# TriggerBoard_v4_rfm12b.net
KiCad netlist of a schematic drawn in EAGLE
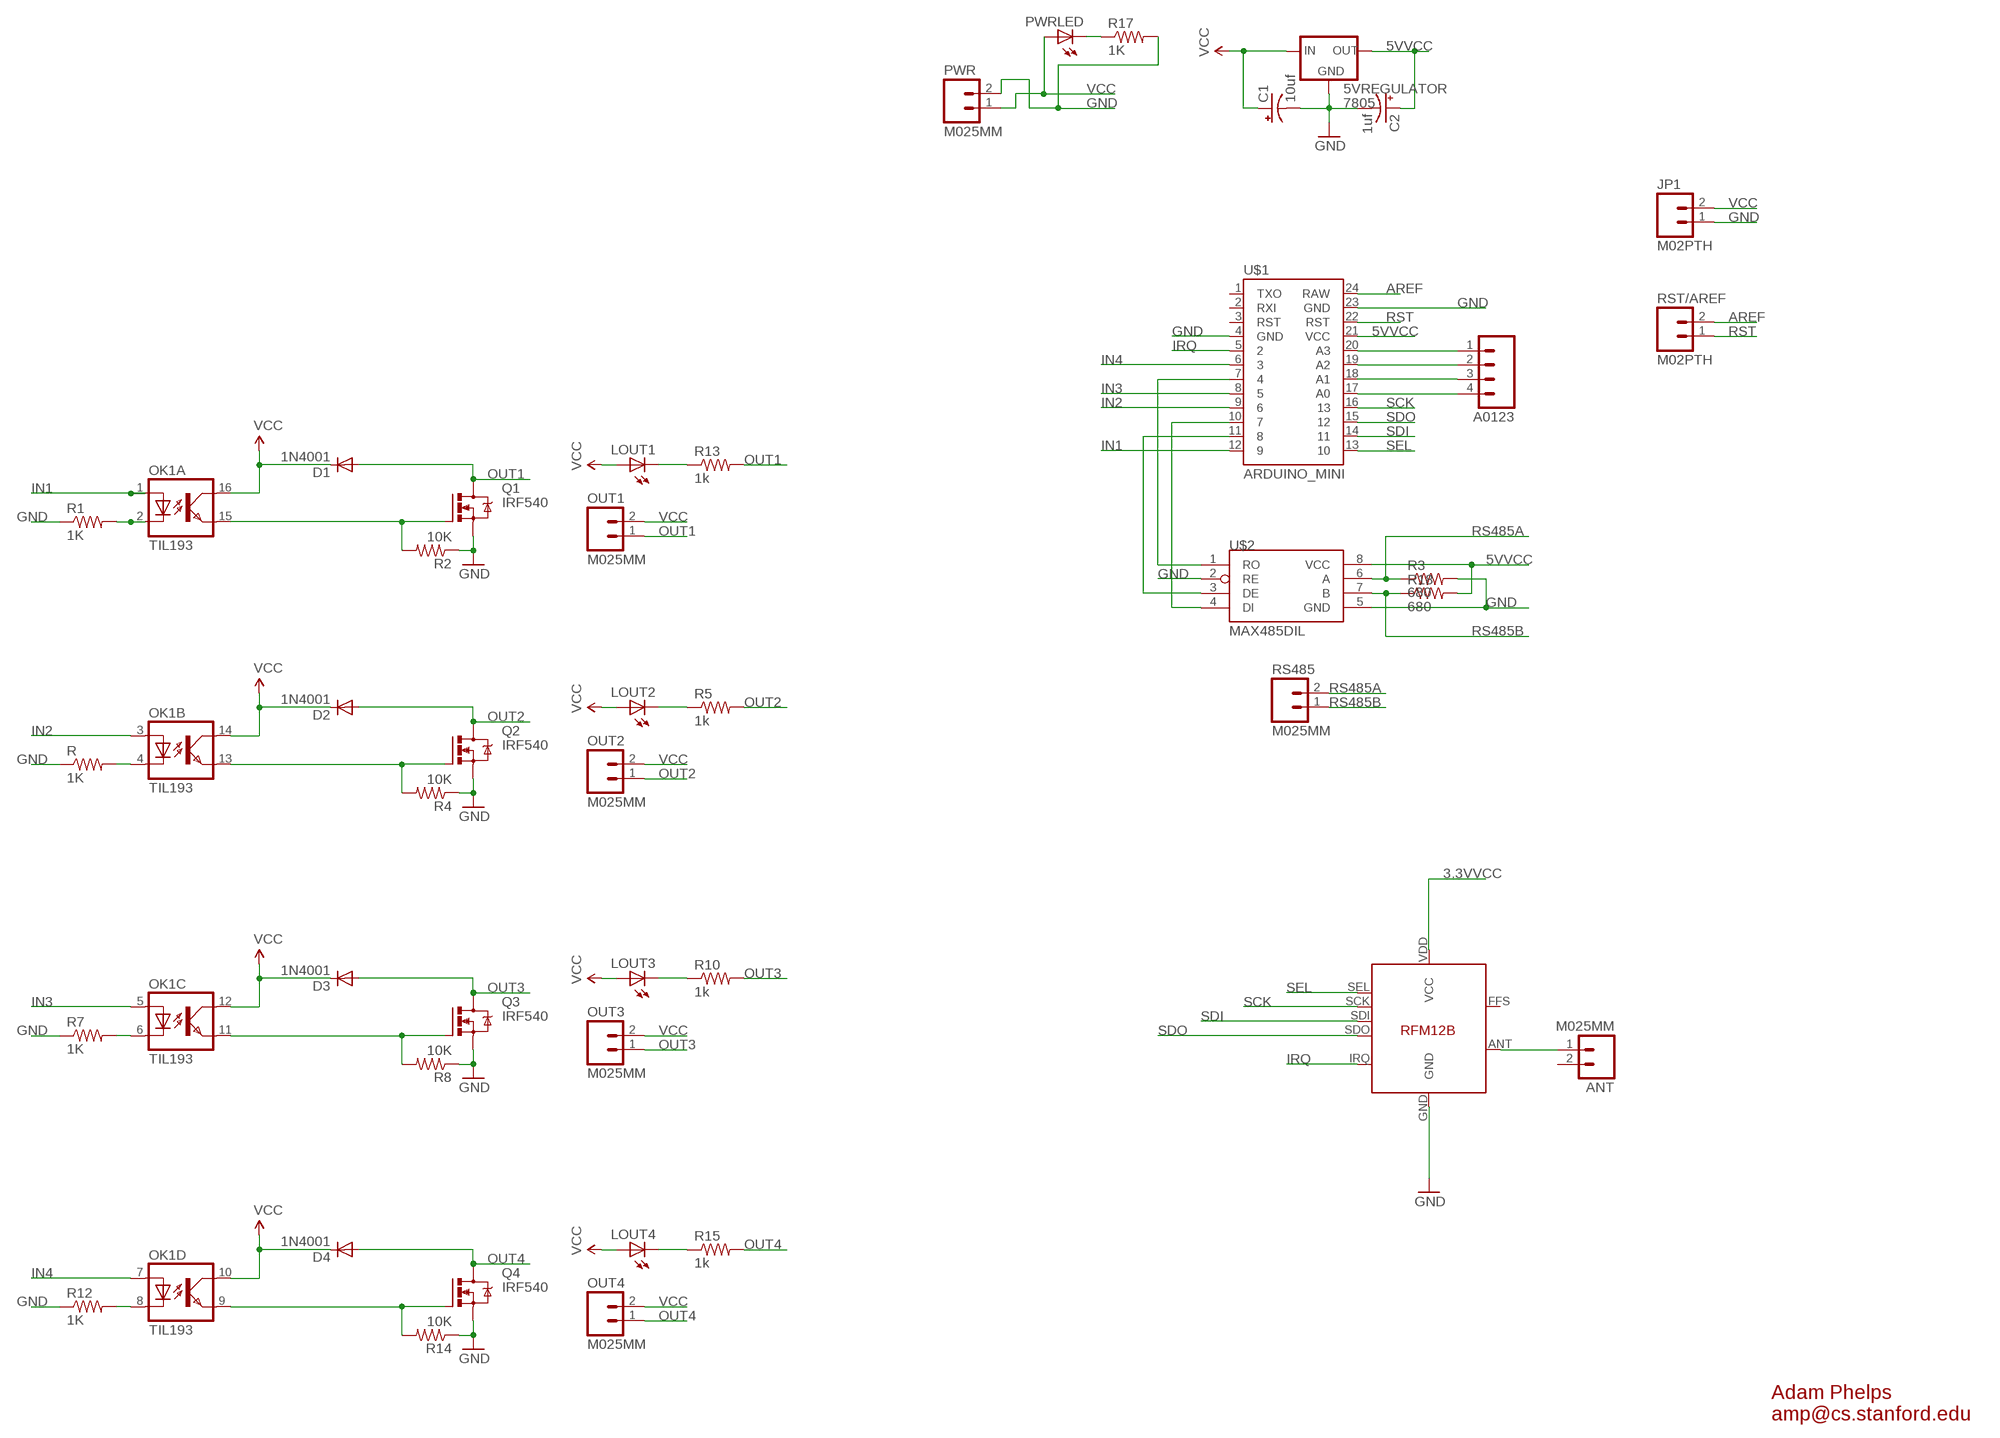
[diagram p0: schematic, sheet 1]

(export (version "E")
  (design (tool "Eeschema 10.0.6"))
  (components
    (comp (ref "5VREGULATOR")
      (value "7805")
      (footprint "eagle-import:TO220-IGO")
      (libsource (lib "eagle-import") (part "V_REG_78XXSINK"))
    )
    (comp (ref "A0123")
      (value "M04PTH")
      (footprint "eagle-import:1X04")
      (libsource (lib "eagle-import") (part "M04PTH"))
    )
    (comp (ref "ANT")
      (value "M025MM")
      (footprint "eagle-import:SCREWTERMINAL-5MM-2")
      (libsource (lib "eagle-import") (part "M025MM"))
    )
    (comp (ref "C1")
      (value "10uf")
      (footprint "eagle-import:CPOL-RADIAL-10UF-25V")
      (libsource (lib "eagle-import") (part "CAP_POLPTH2"))
    )
    (comp (ref "C2")
      (value "1uf")
      (footprint "eagle-import:CPOL-RADIAL-10UF-25V")
      (libsource (lib "eagle-import") (part "CAP_POLPTH2"))
    )
    (comp (ref "D1")
      (value "1N4001")
      (footprint "eagle-import:DIODE-1N4001")
      (libsource (lib "eagle-import") (part "DIODEPTH"))
    )
    (comp (ref "D2")
      (value "1N4001")
      (footprint "eagle-import:DIODE-1N4001")
      (libsource (lib "eagle-import") (part "DIODEPTH"))
    )
    (comp (ref "D3")
      (value "1N4001")
      (footprint "eagle-import:DIODE-1N4001")
      (libsource (lib "eagle-import") (part "DIODEPTH"))
    )
    (comp (ref "D4")
      (value "1N4001")
      (footprint "eagle-import:DIODE-1N4001")
      (libsource (lib "eagle-import") (part "DIODEPTH"))
    )
    (comp (ref "JP1")
      (value "M02PTH")
      (footprint "eagle-import:1X02")
      (libsource (lib "eagle-import") (part "M02PTH"))
    )
    (comp (ref "LOUT1")
      (value "LED3MM")
      (footprint "eagle-import:LED3MM")
      (libsource (lib "eagle-import") (part "LED3MM"))
    )
    (comp (ref "LOUT2")
      (value "LED3MM")
      (footprint "eagle-import:LED3MM")
      (libsource (lib "eagle-import") (part "LED3MM"))
    )
    (comp (ref "LOUT3")
      (value "LED3MM")
      (footprint "eagle-import:LED3MM")
      (libsource (lib "eagle-import") (part "LED3MM"))
    )
    (comp (ref "LOUT4")
      (value "LED3MM")
      (footprint "eagle-import:LED3MM")
      (libsource (lib "eagle-import") (part "LED3MM"))
    )
    (comp (ref "OK1")
      (value "TIL193")
      (footprint "eagle-import:DIL16")
      (libsource (lib "eagle-import") (part "TIL193"))
    )
    (comp (ref "OUT1")
      (value "M025MM")
      (footprint "eagle-import:SCREWTERMINAL-5MM-2")
      (libsource (lib "eagle-import") (part "M025MM"))
    )
    (comp (ref "OUT2")
      (value "M025MM")
      (footprint "eagle-import:SCREWTERMINAL-5MM-2")
      (libsource (lib "eagle-import") (part "M025MM"))
    )
    (comp (ref "OUT3")
      (value "M025MM")
      (footprint "eagle-import:SCREWTERMINAL-5MM-2")
      (libsource (lib "eagle-import") (part "M025MM"))
    )
    (comp (ref "OUT4")
      (value "M025MM")
      (footprint "eagle-import:SCREWTERMINAL-5MM-2")
      (libsource (lib "eagle-import") (part "M025MM"))
    )
    (comp (ref "PWR")
      (value "M025MM")
      (footprint "eagle-import:SCREWTERMINAL-5MM-2")
      (libsource (lib "eagle-import") (part "M025MM"))
    )
    (comp (ref "PWRLED")
      (value "LED5MM")
      (footprint "eagle-import:LED5MM")
      (libsource (lib "eagle-import") (part "LED5MM"))
    )
    (comp (ref "Q1")
      (value "IRF540")
      (footprint "eagle-import:TO220BV")
      (libsource (lib "eagle-import") (part "IRF540"))
    )
    (comp (ref "Q2")
      (value "IRF540")
      (footprint "eagle-import:TO220BV")
      (libsource (lib "eagle-import") (part "IRF540"))
    )
    (comp (ref "Q3")
      (value "IRF540")
      (footprint "eagle-import:TO220BV")
      (libsource (lib "eagle-import") (part "IRF540"))
    )
    (comp (ref "Q4")
      (value "IRF540")
      (footprint "eagle-import:TO220BV")
      (libsource (lib "eagle-import") (part "IRF540"))
    )
    (comp (ref "R")
      (value "1K")
      (footprint "eagle-import:AXIAL-0.4")
      (libsource (lib "eagle-import") (part "RESISTORPTH-1/4W"))
    )
    (comp (ref "R1")
      (value "1K")
      (footprint "eagle-import:AXIAL-0.4")
      (libsource (lib "eagle-import") (part "RESISTORPTH-1/4W"))
    )
    (comp (ref "R2")
      (value "10K")
      (footprint "eagle-import:AXIAL-0.4")
      (libsource (lib "eagle-import") (part "RESISTORPTH-1/4W"))
    )
    (comp (ref "R3")
      (value "680")
      (footprint "eagle-import:AXIAL-0.4")
      (libsource (lib "eagle-import") (part "RESISTORPTH-1/4W"))
    )
    (comp (ref "R4")
      (value "10K")
      (footprint "eagle-import:AXIAL-0.4")
      (libsource (lib "eagle-import") (part "RESISTORPTH-1/4W"))
    )
    (comp (ref "R5")
      (value "1k")
      (footprint "eagle-import:AXIAL-0.4")
      (libsource (lib "eagle-import") (part "RESISTORPTH-1/4W"))
    )
    (comp (ref "R7")
      (value "1K")
      (footprint "eagle-import:AXIAL-0.4")
      (libsource (lib "eagle-import") (part "RESISTORPTH-1/4W"))
    )
    (comp (ref "R8")
      (value "10K")
      (footprint "eagle-import:AXIAL-0.4")
      (libsource (lib "eagle-import") (part "RESISTORPTH-1/4W"))
    )
    (comp (ref "R10")
      (value "1k")
      (footprint "eagle-import:AXIAL-0.4")
      (libsource (lib "eagle-import") (part "RESISTORPTH-1/4W"))
    )
    (comp (ref "R12")
      (value "1K")
      (footprint "eagle-import:AXIAL-0.4")
      (libsource (lib "eagle-import") (part "RESISTORPTH-1/4W"))
    )
    (comp (ref "R13")
      (value "1k")
      (footprint "eagle-import:AXIAL-0.4")
      (libsource (lib "eagle-import") (part "RESISTORPTH-1/4W"))
    )
    (comp (ref "R14")
      (value "10K")
      (footprint "eagle-import:AXIAL-0.4")
      (libsource (lib "eagle-import") (part "RESISTORPTH-1/4W"))
    )
    (comp (ref "R15")
      (value "1k")
      (footprint "eagle-import:AXIAL-0.4")
      (libsource (lib "eagle-import") (part "RESISTORPTH-1/4W"))
    )
    (comp (ref "R17")
      (value "1K")
      (footprint "eagle-import:AXIAL-0.4")
      (libsource (lib "eagle-import") (part "RESISTORPTH-1/4W"))
    )
    (comp (ref "R18")
      (value "680")
      (footprint "eagle-import:AXIAL-0.4")
      (libsource (lib "eagle-import") (part "RESISTORPTH-1/4W"))
    )
    (comp (ref "RS485")
      (value "M025MM")
      (footprint "eagle-import:SCREWTERMINAL-5MM-2")
      (libsource (lib "eagle-import") (part "M025MM"))
    )
    (comp (ref "RST/AREF")
      (value "M02PTH")
      (footprint "eagle-import:1X02")
      (libsource (lib "eagle-import") (part "M02PTH"))
    )
    (comp (ref "U$1")
      (value "ARDUINO_MINI")
      (footprint "eagle-import:ARDUINO_MINI")
      (libsource (lib "eagle-import") (part "ARDUINO_MINI"))
    )
    (comp (ref "U$2")
      (value "MAX485DIL")
      (footprint "eagle-import:DIL08")
      (libsource (lib "eagle-import") (part "MAX485DIL"))
    )
    (comp (ref "U$3")
      (value "RFM12B")
      (footprint "eagle-import:RFM12B")
      (libsource (lib "eagle-import") (part "RFM12B"))
    )
  )
  (nets
    (net (code "1") (name "/3.3VVCC") (class "Default")
      (node (ref "U$3") (pin "VDD") (pinfunction "VCC_VDD") (pintype "power_in"))
    )
    (net (code "2") (name "/5VVCC") (class "Default")
      (node (ref "5VREGULATOR") (pin "OUT") (pinfunction "OUT_OUT") (pintype "output"))
      (node (ref "C2") (pin "1") (pinfunction "+_1") (pintype "passive"))
      (node (ref "R18") (pin "P$2") (pinfunction "2_P$2") (pintype "passive"))
      (node (ref "U$1") (pin "21") (pinfunction "VCC_21") (pintype "bidirectional"))
      (node (ref "U$2") (pin "8") (pinfunction "VCC_8") (pintype "bidirectional"))
    )
    (net (code "3") (name "/AREF") (class "Default")
      (node (ref "RST/AREF") (pin "2") (pinfunction "2_2") (pintype "passive"))
      (node (ref "U$1") (pin "24") (pinfunction "RAW_24") (pintype "bidirectional"))
    )
    (net (code "4") (name "/IN1") (class "Default")
      (node (ref "OK1") (pin "1") (pinfunction "A_1") (pintype "passive"))
      (node (ref "U$1") (pin "12") (pinfunction "9_12") (pintype "bidirectional"))
    )
    (net (code "5") (name "/IN2") (class "Default")
      (node (ref "OK1") (pin "3") (pinfunction "A_3") (pintype "passive"))
      (node (ref "U$1") (pin "9") (pinfunction "6_9") (pintype "bidirectional"))
    )
    (net (code "6") (name "/IN3") (class "Default")
      (node (ref "OK1") (pin "5") (pinfunction "A_5") (pintype "passive"))
      (node (ref "U$1") (pin "8") (pinfunction "5_8") (pintype "bidirectional"))
    )
    (net (code "7") (name "/IN4") (class "Default")
      (node (ref "OK1") (pin "7") (pinfunction "A_7") (pintype "passive"))
      (node (ref "U$1") (pin "6") (pinfunction "3_6") (pintype "bidirectional"))
    )
    (net (code "8") (name "/IRQ") (class "Default")
      (node (ref "U$1") (pin "5") (pinfunction "2_5") (pintype "bidirectional"))
      (node (ref "U$3") (pin "IRQ") (pinfunction "IRQ_IRQ") (pintype "open_collector"))
    )
    (net (code "9") (name "/OUT1") (class "Default")
      (node (ref "D1") (pin "A") (pinfunction "A_A") (pintype "passive"))
      (node (ref "OUT1") (pin "1") (pinfunction "1_1") (pintype "passive"))
      (node (ref "Q1") (pin "D") (pinfunction "D_D") (pintype "passive"))
      (node (ref "R13") (pin "P$2") (pinfunction "2_P$2") (pintype "passive"))
    )
    (net (code "10") (name "/OUT2") (class "Default")
      (node (ref "D2") (pin "A") (pinfunction "A_A") (pintype "passive"))
      (node (ref "OUT2") (pin "1") (pinfunction "1_1") (pintype "passive"))
      (node (ref "Q2") (pin "D") (pinfunction "D_D") (pintype "passive"))
      (node (ref "R5") (pin "P$2") (pinfunction "2_P$2") (pintype "passive"))
    )
    (net (code "11") (name "/OUT3") (class "Default")
      (node (ref "D3") (pin "A") (pinfunction "A_A") (pintype "passive"))
      (node (ref "OUT3") (pin "1") (pinfunction "1_1") (pintype "passive"))
      (node (ref "Q3") (pin "D") (pinfunction "D_D") (pintype "passive"))
      (node (ref "R10") (pin "P$2") (pinfunction "2_P$2") (pintype "passive"))
    )
    (net (code "12") (name "/OUT4") (class "Default")
      (node (ref "D4") (pin "A") (pinfunction "A_A") (pintype "passive"))
      (node (ref "OUT4") (pin "1") (pinfunction "1_1") (pintype "passive"))
      (node (ref "Q4") (pin "D") (pinfunction "D_D") (pintype "passive"))
      (node (ref "R15") (pin "P$2") (pinfunction "2_P$2") (pintype "passive"))
    )
    (net (code "13") (name "/RS485A") (class "Default")
      (node (ref "R3") (pin "P$1") (pinfunction "1_P$1") (pintype "passive"))
      (node (ref "RS485") (pin "2") (pinfunction "2_2") (pintype "passive"))
      (node (ref "U$2") (pin "6") (pinfunction "A_6") (pintype "bidirectional"))
    )
    (net (code "14") (name "/RS485B") (class "Default")
      (node (ref "R18") (pin "P$1") (pinfunction "1_P$1") (pintype "passive"))
      (node (ref "RS485") (pin "1") (pinfunction "1_1") (pintype "passive"))
      (node (ref "U$2") (pin "7") (pinfunction "B_7") (pintype "bidirectional"))
    )
    (net (code "15") (name "/RST") (class "Default")
      (node (ref "RST/AREF") (pin "1") (pinfunction "1_1") (pintype "passive"))
      (node (ref "U$1") (pin "22") (pinfunction "RST_22") (pintype "bidirectional"))
    )
    (net (code "16") (name "/SCK") (class "Default")
      (node (ref "U$1") (pin "16") (pinfunction "13_16") (pintype "bidirectional"))
      (node (ref "U$3") (pin "SCK") (pinfunction "SCK_SCK") (pintype "input"))
    )
    (net (code "17") (name "/SDI") (class "Default")
      (node (ref "U$1") (pin "14") (pinfunction "11_14") (pintype "bidirectional"))
      (node (ref "U$3") (pin "SDI") (pinfunction "SDI_SDI") (pintype "input"))
    )
    (net (code "18") (name "/SDO") (class "Default")
      (node (ref "U$1") (pin "15") (pinfunction "12_15") (pintype "bidirectional"))
      (node (ref "U$3") (pin "SDO") (pinfunction "SDO_SDO") (pintype "output"))
    )
    (net (code "19") (name "/SEL") (class "Default")
      (node (ref "U$1") (pin "13") (pinfunction "10_13") (pintype "bidirectional"))
      (node (ref "U$3") (pin "SEL") (pinfunction "SEL_SEL") (pintype "input"))
    )
    (net (code "20") (name "GND") (class "Default")
      (node (ref "5VREGULATOR") (pin "GND") (pinfunction "GND_GND") (pintype "input"))
      (node (ref "C1") (pin "2") (pinfunction "-_2") (pintype "passive"))
      (node (ref "C2") (pin "2") (pinfunction "-_2") (pintype "passive"))
      (node (ref "JP1") (pin "1") (pinfunction "1_1") (pintype "passive"))
      (node (ref "PWR") (pin "2") (pinfunction "2_2") (pintype "passive"))
      (node (ref "Q1") (pin "S") (pinfunction "S_S") (pintype "passive"))
      (node (ref "Q2") (pin "S") (pinfunction "S_S") (pintype "passive"))
      (node (ref "Q3") (pin "S") (pinfunction "S_S") (pintype "passive"))
      (node (ref "Q4") (pin "S") (pinfunction "S_S") (pintype "passive"))
      (node (ref "R") (pin "P$1") (pinfunction "1_P$1") (pintype "passive"))
      (node (ref "R1") (pin "P$1") (pinfunction "1_P$1") (pintype "passive"))
      (node (ref "R12") (pin "P$1") (pinfunction "1_P$1") (pintype "passive"))
      (node (ref "R14") (pin "P$1") (pinfunction "1_P$1") (pintype "passive"))
      (node (ref "R17") (pin "P$2") (pinfunction "2_P$2") (pintype "passive"))
      (node (ref "R2") (pin "P$1") (pinfunction "1_P$1") (pintype "passive"))
      (node (ref "R3") (pin "P$2") (pinfunction "2_P$2") (pintype "passive"))
      (node (ref "R4") (pin "P$1") (pinfunction "1_P$1") (pintype "passive"))
      (node (ref "R7") (pin "P$1") (pinfunction "1_P$1") (pintype "passive"))
      (node (ref "R8") (pin "P$1") (pinfunction "1_P$1") (pintype "passive"))
      (node (ref "U$1") (pin "23") (pinfunction "GND_23") (pintype "bidirectional"))
      (node (ref "U$1") (pin "4") (pinfunction "GND_4") (pintype "bidirectional"))
      (node (ref "U$2") (pin "2") (pinfunction "RE_2") (pintype "bidirectional"))
      (node (ref "U$2") (pin "5") (pinfunction "GND_5") (pintype "bidirectional"))
      (node (ref "U$3") (pin "GND") (pinfunction "GND_GND") (pintype "power_in"))
    )
    (net (code "21") (name "Net-(ANT-Pad1)") (class "Default")
      (node (ref "ANT") (pin "1") (pinfunction "1_1") (pintype "passive"))
      (node (ref "U$3") (pin "ANT") (pinfunction "ANT_ANT") (pintype "passive"))
    )
    (net (code "22") (name "Net-(LOUT1-C)") (class "Default")
      (node (ref "LOUT1") (pin "K") (pinfunction "C_K") (pintype "passive"))
      (node (ref "R13") (pin "P$1") (pinfunction "1_P$1") (pintype "passive"))
    )
    (net (code "23") (name "Net-(LOUT2-C)") (class "Default")
      (node (ref "LOUT2") (pin "K") (pinfunction "C_K") (pintype "passive"))
      (node (ref "R5") (pin "P$1") (pinfunction "1_P$1") (pintype "passive"))
    )
    (net (code "24") (name "Net-(LOUT3-C)") (class "Default")
      (node (ref "LOUT3") (pin "K") (pinfunction "C_K") (pintype "passive"))
      (node (ref "R10") (pin "P$1") (pinfunction "1_P$1") (pintype "passive"))
    )
    (net (code "25") (name "Net-(LOUT4-C)") (class "Default")
      (node (ref "LOUT4") (pin "K") (pinfunction "C_K") (pintype "passive"))
      (node (ref "R15") (pin "P$1") (pinfunction "1_P$1") (pintype "passive"))
    )
    (net (code "26") (name "Net-(OK1A-C)") (class "Default")
      (node (ref "OK1") (pin "2") (pinfunction "C_2") (pintype "passive"))
      (node (ref "R1") (pin "P$2") (pinfunction "2_P$2") (pintype "passive"))
    )
    (net (code "27") (name "Net-(OK1A-EMIT)") (class "Default")
      (node (ref "OK1") (pin "15") (pinfunction "EMIT_15") (pintype "passive"))
      (node (ref "Q1") (pin "G") (pinfunction "G_G") (pintype "passive"))
      (node (ref "R2") (pin "P$2") (pinfunction "2_P$2") (pintype "passive"))
    )
    (net (code "28") (name "Net-(OK1B-C)") (class "Default")
      (node (ref "OK1") (pin "4") (pinfunction "C_4") (pintype "passive"))
      (node (ref "R") (pin "P$2") (pinfunction "2_P$2") (pintype "passive"))
    )
    (net (code "29") (name "Net-(OK1B-EMIT)") (class "Default")
      (node (ref "OK1") (pin "13") (pinfunction "EMIT_13") (pintype "passive"))
      (node (ref "Q2") (pin "G") (pinfunction "G_G") (pintype "passive"))
      (node (ref "R4") (pin "P$2") (pinfunction "2_P$2") (pintype "passive"))
    )
    (net (code "30") (name "Net-(OK1C-C)") (class "Default")
      (node (ref "OK1") (pin "6") (pinfunction "C_6") (pintype "passive"))
      (node (ref "R7") (pin "P$2") (pinfunction "2_P$2") (pintype "passive"))
    )
    (net (code "31") (name "Net-(OK1C-EMIT)") (class "Default")
      (node (ref "OK1") (pin "11") (pinfunction "EMIT_11") (pintype "passive"))
      (node (ref "Q3") (pin "G") (pinfunction "G_G") (pintype "passive"))
      (node (ref "R8") (pin "P$2") (pinfunction "2_P$2") (pintype "passive"))
    )
    (net (code "32") (name "Net-(OK1D-C)") (class "Default")
      (node (ref "OK1") (pin "8") (pinfunction "C_8") (pintype "passive"))
      (node (ref "R12") (pin "P$2") (pinfunction "2_P$2") (pintype "passive"))
    )
    (net (code "33") (name "Net-(OK1D-EMIT)") (class "Default")
      (node (ref "OK1") (pin "9") (pinfunction "EMIT_9") (pintype "passive"))
      (node (ref "Q4") (pin "G") (pinfunction "G_G") (pintype "passive"))
      (node (ref "R14") (pin "P$2") (pinfunction "2_P$2") (pintype "passive"))
    )
    (net (code "34") (name "Net-(PWRLED-C)") (class "Default")
      (node (ref "PWRLED") (pin "K") (pinfunction "C_K") (pintype "passive"))
      (node (ref "R17") (pin "P$1") (pinfunction "1_P$1") (pintype "passive"))
    )
    (net (code "35") (name "Net-(U$1-4)") (class "Default")
      (node (ref "U$1") (pin "7") (pinfunction "4_7") (pintype "bidirectional"))
      (node (ref "U$2") (pin "1") (pinfunction "RO_1") (pintype "bidirectional"))
    )
    (net (code "36") (name "Net-(U$1-7)") (class "Default")
      (node (ref "U$1") (pin "10") (pinfunction "7_10") (pintype "bidirectional"))
      (node (ref "U$2") (pin "4") (pinfunction "DI_4") (pintype "bidirectional"))
    )
    (net (code "37") (name "Net-(U$1-8)") (class "Default")
      (node (ref "U$1") (pin "11") (pinfunction "8_11") (pintype "bidirectional"))
      (node (ref "U$2") (pin "3") (pinfunction "DE_3") (pintype "bidirectional"))
    )
    (net (code "38") (name "Net-(U$1-A0)") (class "Default")
      (node (ref "A0123") (pin "4") (pinfunction "4_4") (pintype "passive"))
      (node (ref "U$1") (pin "17") (pinfunction "A0_17") (pintype "bidirectional"))
    )
    (net (code "39") (name "Net-(U$1-A1)") (class "Default")
      (node (ref "A0123") (pin "3") (pinfunction "3_3") (pintype "passive"))
      (node (ref "U$1") (pin "18") (pinfunction "A1_18") (pintype "bidirectional"))
    )
    (net (code "40") (name "Net-(U$1-A2)") (class "Default")
      (node (ref "A0123") (pin "2") (pinfunction "2_2") (pintype "passive"))
      (node (ref "U$1") (pin "19") (pinfunction "A2_19") (pintype "bidirectional"))
    )
    (net (code "41") (name "Net-(U$1-A3)") (class "Default")
      (node (ref "A0123") (pin "1") (pinfunction "1_1") (pintype "passive"))
      (node (ref "U$1") (pin "20") (pinfunction "A3_20") (pintype "bidirectional"))
    )
    (net (code "42") (name "VCC") (class "Default")
      (node (ref "5VREGULATOR") (pin "IN") (pinfunction "IN_IN") (pintype "input"))
      (node (ref "C1") (pin "1") (pinfunction "+_1") (pintype "passive"))
      (node (ref "D1") (pin "C") (pinfunction "C_C") (pintype "passive"))
      (node (ref "D2") (pin "C") (pinfunction "C_C") (pintype "passive"))
      (node (ref "D3") (pin "C") (pinfunction "C_C") (pintype "passive"))
      (node (ref "D4") (pin "C") (pinfunction "C_C") (pintype "passive"))
      (node (ref "JP1") (pin "2") (pinfunction "2_2") (pintype "passive"))
      (node (ref "LOUT1") (pin "A") (pinfunction "A_A") (pintype "passive"))
      (node (ref "LOUT2") (pin "A") (pinfunction "A_A") (pintype "passive"))
      (node (ref "LOUT3") (pin "A") (pinfunction "A_A") (pintype "passive"))
      (node (ref "LOUT4") (pin "A") (pinfunction "A_A") (pintype "passive"))
      (node (ref "OK1") (pin "10") (pinfunction "COL_10") (pintype "passive"))
      (node (ref "OK1") (pin "12") (pinfunction "COL_12") (pintype "passive"))
      (node (ref "OK1") (pin "14") (pinfunction "COL_14") (pintype "passive"))
      (node (ref "OK1") (pin "16") (pinfunction "COL_16") (pintype "passive"))
      (node (ref "OUT1") (pin "2") (pinfunction "2_2") (pintype "passive"))
      (node (ref "OUT2") (pin "2") (pinfunction "2_2") (pintype "passive"))
      (node (ref "OUT3") (pin "2") (pinfunction "2_2") (pintype "passive"))
      (node (ref "OUT4") (pin "2") (pinfunction "2_2") (pintype "passive"))
      (node (ref "PWR") (pin "1") (pinfunction "1_1") (pintype "passive"))
      (node (ref "PWRLED") (pin "A") (pinfunction "A_A") (pintype "passive"))
    )
    (net (code "43") (name "unconnected-(ANT-Pad2)") (class "Default")
      (node (ref "ANT") (pin "2") (pinfunction "2_2") (pintype "passive"))
    )
    (net (code "44") (name "unconnected-(U$1-RST-Pad3)") (class "Default")
      (node (ref "U$1") (pin "3") (pinfunction "RST_3") (pintype "bidirectional"))
    )
    (net (code "45") (name "unconnected-(U$1-RXI-Pad2)") (class "Default")
      (node (ref "U$1") (pin "2") (pinfunction "RXI_2") (pintype "bidirectional"))
    )
    (net (code "46") (name "unconnected-(U$1-TXO-Pad1)") (class "Default")
      (node (ref "U$1") (pin "1") (pinfunction "TXO_1") (pintype "bidirectional"))
    )
    (net (code "47") (name "unconnected-(U$3-PadFFS)") (class "Default")
      (node (ref "U$3") (pin "FFS") (pinfunction "FFS_FFS") (pintype "bidirectional"))
    )
  )
)
